# PAPOWER.net
KiCad netlist of a schematic drawn in Altium Designer
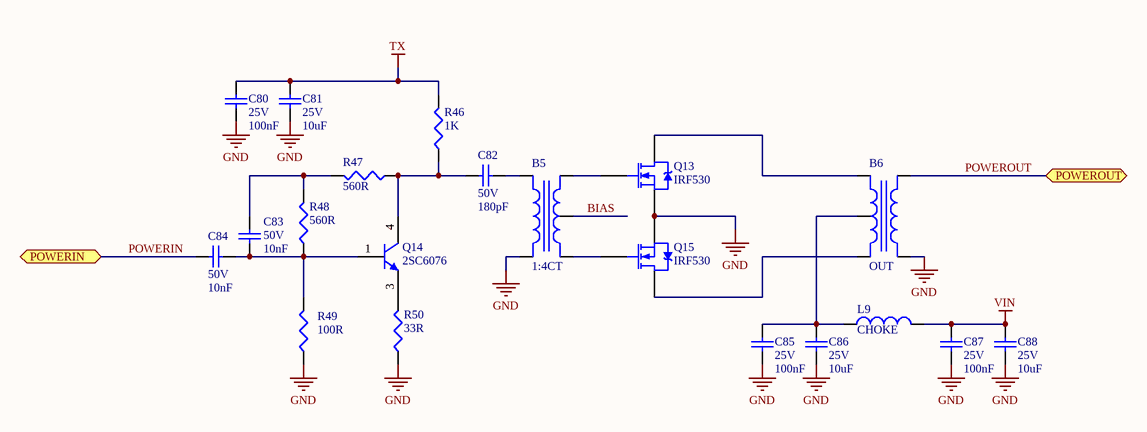
[diagram p0: PAPOWER.SchDoc]

(export (version "E")
  (design (tool "Eeschema 10.0.6"))
  (components
    (comp (ref "B5")
      (value "1:4CT")
      (footprint "CX2047LANL")
      (description "Balun 4CT:1")
      (libsource (lib "NavarroIND") (part "BALUN CX2047LANL"))
    )
    (comp (ref "B6")
      (value "OUT")
      (footprint "T37-43-5")
      (description "Balun PA")
      (libsource (lib "NavarroIND") (part "BALUN OUTPUT"))
    )
    (comp (ref "C80")
      (value "100nF")
      (footprint "CC0603")
      (description "Capacitor (Semiconductor SIM Model)")
      (fields (field (name "TENSÃO") "25V") (field (name "Comment") "Capacitor Cerâmico"))
      (libsource (lib "NavarroCAP") (part "Cap 100nF 25V 0603 X7R"))
    )
    (comp (ref "C81")
      (value "10uF")
      (footprint "CC0805")
      (description "Capacitor (Semiconductor SIM Model)")
      (fields (field (name "TENSÃO") "25V") (field (name "Comment") "Capacitor Cerâmico"))
      (libsource (lib "NavarroCAP") (part "Cap 10uF 25V 0805 X5R"))
    )
    (comp (ref "C82")
      (value "180pF")
      (footprint "CC0603")
      (description "Capacitor (Semiconductor SIM Model)")
      (fields (field (name "TENSÃO") "50V") (field (name "Comment") "Capacitor Cerâmico"))
      (libsource (lib "NavarroCAP") (part "Cap 180pF 50V 0603 NP0"))
    )
    (comp (ref "C83")
      (value "10nF")
      (footprint "CC0603")
      (description "Capacitor (Semiconductor SIM Model)")
      (fields (field (name "TENSÃO") "50V") (field (name "Comment") "Capacitor Cerâmico"))
      (libsource (lib "NavarroCAP") (part "Cap 10nF 50V 0603 X7R 5%"))
    )
    (comp (ref "C84")
      (value "10nF")
      (footprint "CC0603")
      (description "Capacitor (Semiconductor SIM Model)")
      (fields (field (name "TENSÃO") "50V") (field (name "Comment") "Capacitor Cerâmico"))
      (libsource (lib "NavarroCAP") (part "Cap 10nF 50V 0603 X7R 5%"))
    )
    (comp (ref "C85")
      (value "100nF")
      (footprint "CC0603")
      (description "Capacitor (Semiconductor SIM Model)")
      (fields (field (name "TENSÃO") "25V") (field (name "Comment") "Capacitor Cerâmico"))
      (libsource (lib "NavarroCAP") (part "Cap 100nF 25V 0603 X7R"))
    )
    (comp (ref "C86")
      (value "10uF")
      (footprint "CC0805")
      (description "Capacitor (Semiconductor SIM Model)")
      (fields (field (name "TENSÃO") "25V") (field (name "Comment") "Capacitor Cerâmico"))
      (libsource (lib "NavarroCAP") (part "Cap 10uF 25V 0805 X5R"))
    )
    (comp (ref "C87")
      (value "100nF")
      (footprint "CC0603")
      (description "Capacitor (Semiconductor SIM Model)")
      (fields (field (name "TENSÃO") "25V") (field (name "Comment") "Capacitor Cerâmico"))
      (libsource (lib "NavarroCAP") (part "Cap 100nF 25V 0603 X7R"))
    )
    (comp (ref "C88")
      (value "10uF")
      (footprint "CC0805")
      (description "Capacitor (Semiconductor SIM Model)")
      (fields (field (name "TENSÃO") "25V") (field (name "Comment") "Capacitor Cerâmico"))
      (libsource (lib "NavarroCAP") (part "Cap 10uF 25V 0805 X5R"))
    )
    (comp (ref "L9")
      (value "CHOKE")
      (footprint "T37-43-2")
      (description "Bead")
      (libsource (lib "NavarroIND") (part "CHOKE"))
    )
    (comp (ref "Q13")
      (value "IRF530")
      (footprint "TO-220-3N")
      (description "N-Channel Power MOSFET")
      (libsource (lib "NavarroSEMI") (part "TRS IRF530 100V 14A TO-220"))
    )
    (comp (ref "Q14")
      (value "2SC6076")
      (footprint "TO-252")
      (description "NPN General Purpose Amplifier")
      (libsource (lib "NavarroSEMI") (part "TRS 2SC6076 160V 3A TO-252"))
    )
    (comp (ref "Q15")
      (value "IRF530")
      (footprint "TO-220-3N")
      (description "N-Channel Power MOSFET")
      (libsource (lib "NavarroSEMI") (part "TRS IRF530 100V 14A TO-220"))
    )
    (comp (ref "R46")
      (value "1K")
      (footprint "CC0805")
      (description "Resistor")
      (libsource (lib "NavarroRES") (part "Res 1K 1% 0805 1/8W"))
    )
    (comp (ref "R47")
      (value "560R")
      (footprint "CC0603~0805")
      (description "Resistor")
      (libsource (lib "NavarroRES") (part "Res 560R 1% 0603 1/8W"))
    )
    (comp (ref "R48")
      (value "560R")
      (footprint "CC0603~0805")
      (description "Resistor")
      (libsource (lib "NavarroRES") (part "Res 560R 1% 0603 1/8W"))
    )
    (comp (ref "R49")
      (value "100R")
      (footprint "CC0805")
      (description "Resistor")
      (libsource (lib "NavarroRES") (part "Res 100R 5% 0805 1/8W"))
    )
    (comp (ref "R50")
      (value "33R")
      (footprint "CC0603~0805")
      (description "Resistor")
      (libsource (lib "NavarroRES") (part "Res 33R 1% 0603 1/10W"))
    )
  )
  (nets
    (net (code "1") (name "/BIAS") (class "Default")
      (node (ref "B5") (pin "2") (pinfunction "Sec+_2") (pintype "passive"))
    )
    (net (code "2") (name "/POWERIN") (class "Default")
      (node (ref "C84") (pin "1") (pinfunction "1_1") (pintype "passive"))
    )
    (net (code "3") (name "/POWEROUT") (class "Default")
      (node (ref "B6") (pin "4") (pinfunction "Pri+_4") (pintype "passive"))
    )
    (net (code "4") (name "GND") (class "Default")
      (node (ref "B5") (pin "4") (pinfunction "Pri+_4") (pintype "passive"))
      (node (ref "B6") (pin "5") (pinfunction "Sec-_5") (pintype "passive"))
      (node (ref "C80") (pin "1") (pinfunction "1_1") (pintype "passive"))
      (node (ref "C81") (pin "1") (pinfunction "1_1") (pintype "passive"))
      (node (ref "C85") (pin "1") (pinfunction "1_1") (pintype "passive"))
      (node (ref "C86") (pin "1") (pinfunction "1_1") (pintype "passive"))
      (node (ref "C87") (pin "1") (pinfunction "1_1") (pintype "passive"))
      (node (ref "C88") (pin "1") (pinfunction "1_1") (pintype "passive"))
      (node (ref "Q13") (pin "3") (pinfunction "S_3") (pintype "passive"))
      (node (ref "Q15") (pin "3") (pinfunction "S_3") (pintype "passive"))
      (node (ref "R49") (pin "1") (pinfunction "1_1") (pintype "passive"))
      (node (ref "R50") (pin "1") (pinfunction "1_1") (pintype "passive"))
    )
    (net (code "5") (name "Net-(B5-Pri-)") (class "Default")
      (node (ref "B5") (pin "3") (pinfunction "Pri-_3") (pintype "passive"))
      (node (ref "Q15") (pin "1") (pinfunction "G_1") (pintype "passive"))
    )
    (net (code "6") (name "Net-(B5-Sec-)") (class "Default")
      (node (ref "B5") (pin "6") (pinfunction "Sec-_6") (pintype "passive"))
      (node (ref "C82") (pin "2") (pinfunction "2_2") (pintype "passive"))
    )
    (net (code "7") (name "Net-(B6-Pri-)") (class "Default")
      (node (ref "B6") (pin "1") (pinfunction "Pri-_1") (pintype "passive"))
      (node (ref "Q13") (pin "2") (pinfunction "D_2") (pintype "passive"))
    )
    (net (code "8") (name "Net-(B6-Sec+-Pad2)") (class "Default")
      (node (ref "B6") (pin "2") (pinfunction "Sec+_2") (pintype "passive"))
      (node (ref "C85") (pin "2") (pinfunction "2_2") (pintype "passive"))
      (node (ref "C86") (pin "2") (pinfunction "2_2") (pintype "passive"))
      (node (ref "L9") (pin "1") (pinfunction "1_1") (pintype "passive"))
    )
    (net (code "9") (name "Net-(C83-Pad2)") (class "Default")
      (node (ref "C83") (pin "2") (pinfunction "2_2") (pintype "passive"))
      (node (ref "R47") (pin "2") (pinfunction "2_2") (pintype "passive"))
      (node (ref "R48") (pin "2") (pinfunction "2_2") (pintype "passive"))
    )
    (net (code "10") (name "Net-(Q13-G)") (class "Default")
      (node (ref "B5") (pin "1") (pinfunction "Sec+_1") (pintype "passive"))
      (node (ref "Q13") (pin "1") (pinfunction "G_1") (pintype "passive"))
    )
    (net (code "11") (name "Net-(Q14-B)") (class "Default")
      (node (ref "C83") (pin "1") (pinfunction "1_1") (pintype "passive"))
      (node (ref "C84") (pin "2") (pinfunction "2_2") (pintype "passive"))
      (node (ref "Q14") (pin "1") (pinfunction "B_1") (pintype "passive"))
      (node (ref "R48") (pin "1") (pinfunction "1_1") (pintype "passive"))
      (node (ref "R49") (pin "2") (pinfunction "2_2") (pintype "passive"))
    )
    (net (code "12") (name "Net-(Q14-C)") (class "Default")
      (node (ref "C82") (pin "1") (pinfunction "1_1") (pintype "passive"))
      (node (ref "Q14") (pin "4") (pinfunction "C_4") (pintype "passive"))
      (node (ref "R46") (pin "1") (pinfunction "1_1") (pintype "passive"))
      (node (ref "R47") (pin "1") (pinfunction "1_1") (pintype "passive"))
    )
    (net (code "13") (name "Net-(Q14-E)") (class "Default")
      (node (ref "Q14") (pin "3") (pinfunction "E_3") (pintype "passive"))
      (node (ref "R50") (pin "2") (pinfunction "2_2") (pintype "passive"))
    )
    (net (code "14") (name "Net-(Q15-D)") (class "Default")
      (node (ref "B6") (pin "3") (pinfunction "Sec+_3") (pintype "passive"))
      (node (ref "Q15") (pin "2") (pinfunction "D_2") (pintype "passive"))
    )
    (net (code "15") (name "TX") (class "Default")
      (node (ref "C80") (pin "2") (pinfunction "2_2") (pintype "passive"))
      (node (ref "C81") (pin "2") (pinfunction "2_2") (pintype "passive"))
      (node (ref "R46") (pin "2") (pinfunction "2_2") (pintype "passive"))
    )
    (net (code "16") (name "VIN") (class "Default")
      (node (ref "C87") (pin "2") (pinfunction "2_2") (pintype "passive"))
      (node (ref "C88") (pin "2") (pinfunction "2_2") (pintype "passive"))
      (node (ref "L9") (pin "2") (pinfunction "2_2") (pintype "passive"))
    )
  )
)
